# Lemming_SMD.net
KiCad netlist of a schematic drawn in EAGLE
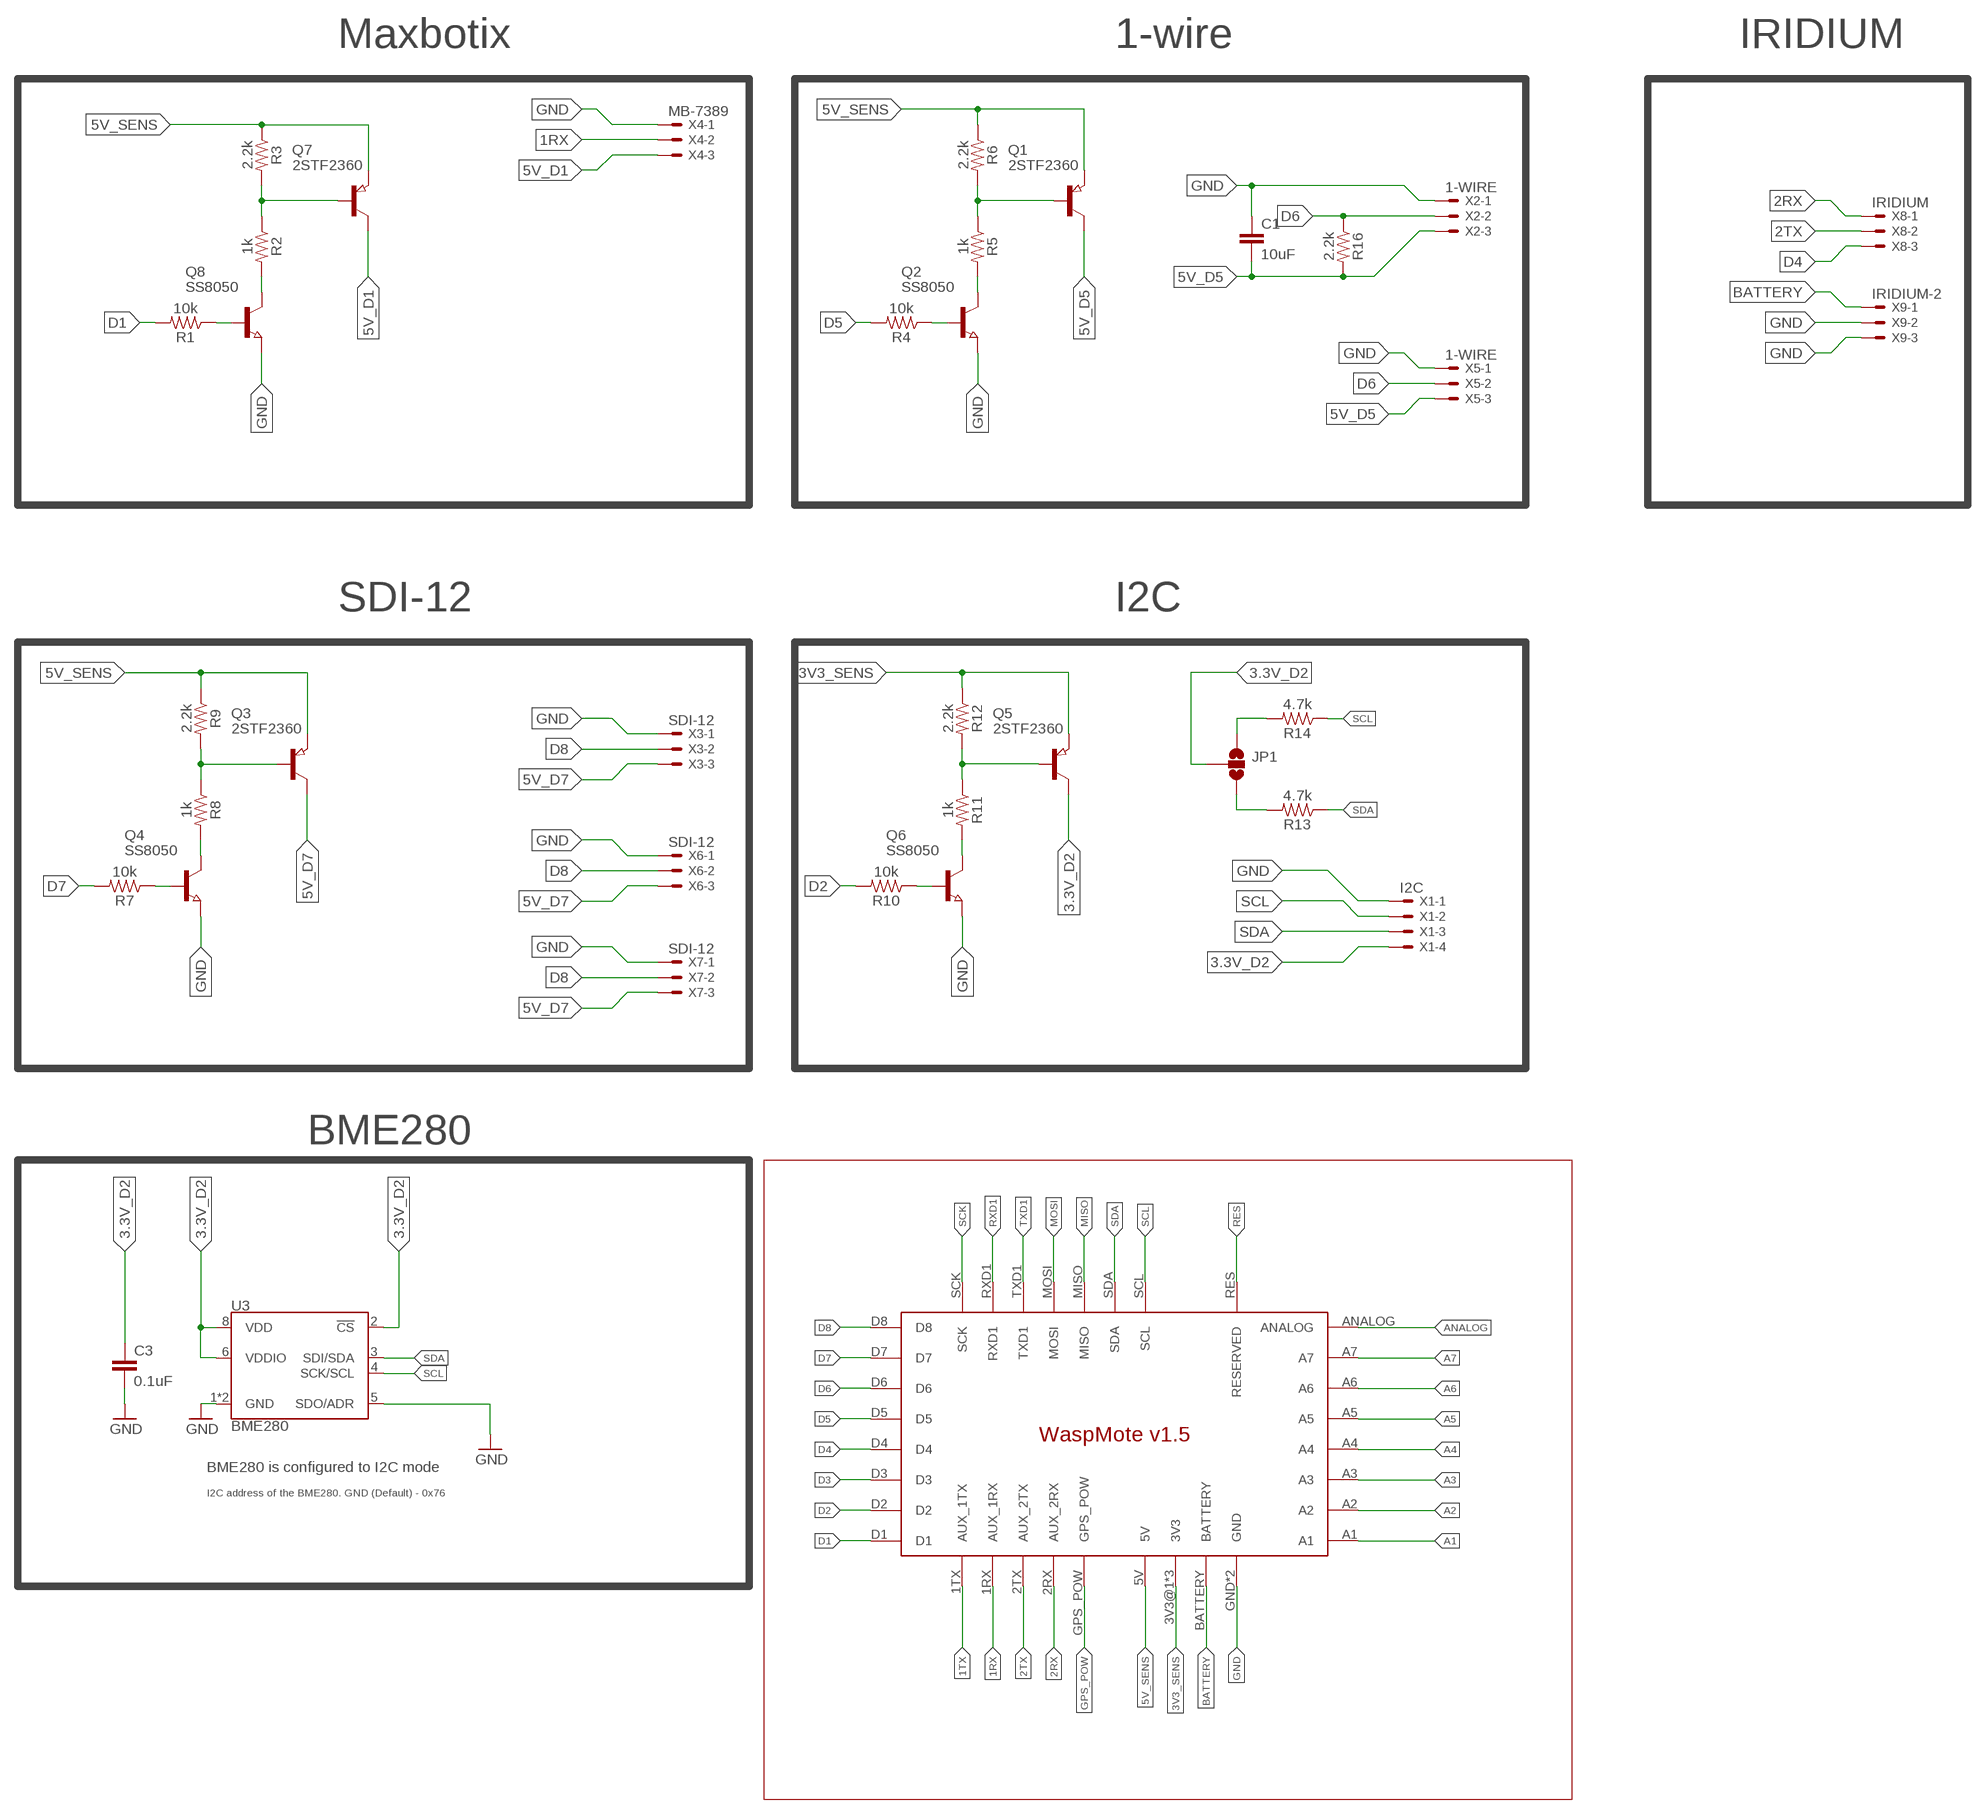
[diagram p0: schematic, sheet 1]

(export (version "E")
  (design (tool "Eeschema 10.0.6"))
  (components
    (comp (ref "C1")
      (value "10uF")
      (footprint "eagle-import:0603")
      (libsource (lib "eagle-import") (part "0.1UF-0603-25V-(+80/-20%)"))
    )
    (comp (ref "C3")
      (value "0.1uF")
      (footprint "eagle-import:0603")
      (libsource (lib "eagle-import") (part "0.1UF-0603-25V-(+80/-20%)"))
    )
    (comp (ref "JP1")
      (value "JUMPER-SMT_3_NO_SILK")
      (footprint "eagle-import:SMT-JUMPER_3_NO_SILK")
      (libsource (lib "eagle-import") (part "JUMPER-SMT_3_NO_SILK"))
    )
    (comp (ref "Q1")
      (value "2STF2360")
      (footprint "eagle-import:SOT89")
      (libsource (lib "eagle-import") (part "PNP-TRANSISTOR_SOT89"))
    )
    (comp (ref "Q2")
      (value "SS8050")
      (footprint "eagle-import:SOT23")
      (libsource (lib "eagle-import") (part "NPN-TRANSISTOR_SOT23"))
    )
    (comp (ref "Q3")
      (value "2STF2360")
      (footprint "eagle-import:SOT89")
      (libsource (lib "eagle-import") (part "PNP-TRANSISTOR_SOT89"))
    )
    (comp (ref "Q4")
      (value "SS8050")
      (footprint "eagle-import:SOT23")
      (libsource (lib "eagle-import") (part "NPN-TRANSISTOR_SOT23"))
    )
    (comp (ref "Q5")
      (value "2STF2360")
      (footprint "eagle-import:SOT89")
      (libsource (lib "eagle-import") (part "PNP-TRANSISTOR_SOT89"))
    )
    (comp (ref "Q6")
      (value "SS8050")
      (footprint "eagle-import:SOT23")
      (libsource (lib "eagle-import") (part "NPN-TRANSISTOR_SOT23"))
    )
    (comp (ref "Q7")
      (value "2STF2360")
      (footprint "eagle-import:SOT89")
      (libsource (lib "eagle-import") (part "PNP-TRANSISTOR_SOT89"))
    )
    (comp (ref "Q8")
      (value "SS8050")
      (footprint "eagle-import:SOT23")
      (libsource (lib "eagle-import") (part "NPN-TRANSISTOR_SOT23"))
    )
    (comp (ref "R1")
      (value "10k")
      (footprint "eagle-import:0603")
      (libsource (lib "eagle-import") (part "4.7KOHM-0603-1/10W-1%"))
    )
    (comp (ref "R2")
      (value "1k")
      (footprint "eagle-import:0603")
      (libsource (lib "eagle-import") (part "4.7KOHM-0603-1/10W-1%"))
    )
    (comp (ref "R3")
      (value "2.2k")
      (footprint "eagle-import:0603")
      (libsource (lib "eagle-import") (part "4.7KOHM-0603-1/10W-1%"))
    )
    (comp (ref "R4")
      (value "10k")
      (footprint "eagle-import:0603")
      (libsource (lib "eagle-import") (part "4.7KOHM-0603-1/10W-1%"))
    )
    (comp (ref "R5")
      (value "1k")
      (footprint "eagle-import:0603")
      (libsource (lib "eagle-import") (part "4.7KOHM-0603-1/10W-1%"))
    )
    (comp (ref "R6")
      (value "2.2k")
      (footprint "eagle-import:0603")
      (libsource (lib "eagle-import") (part "4.7KOHM-0603-1/10W-1%"))
    )
    (comp (ref "R7")
      (value "10k")
      (footprint "eagle-import:0603")
      (libsource (lib "eagle-import") (part "4.7KOHM-0603-1/10W-1%"))
    )
    (comp (ref "R8")
      (value "1k")
      (footprint "eagle-import:0603")
      (libsource (lib "eagle-import") (part "4.7KOHM-0603-1/10W-1%"))
    )
    (comp (ref "R9")
      (value "2.2k")
      (footprint "eagle-import:0603")
      (libsource (lib "eagle-import") (part "4.7KOHM-0603-1/10W-1%"))
    )
    (comp (ref "R10")
      (value "10k")
      (footprint "eagle-import:0603")
      (libsource (lib "eagle-import") (part "4.7KOHM-0603-1/10W-1%"))
    )
    (comp (ref "R11")
      (value "1k")
      (footprint "eagle-import:0603")
      (libsource (lib "eagle-import") (part "4.7KOHM-0603-1/10W-1%"))
    )
    (comp (ref "R12")
      (value "2.2k")
      (footprint "eagle-import:0603")
      (libsource (lib "eagle-import") (part "4.7KOHM-0603-1/10W-1%"))
    )
    (comp (ref "R13")
      (value "4.7k")
      (footprint "eagle-import:0603")
      (libsource (lib "eagle-import") (part "4.7KOHM-0603-1/10W-1%"))
    )
    (comp (ref "R14")
      (value "4.7k")
      (footprint "eagle-import:0603")
      (libsource (lib "eagle-import") (part "4.7KOHM-0603-1/10W-1%"))
    )
    (comp (ref "R16")
      (value "2.2k")
      (footprint "eagle-import:0603")
      (libsource (lib "eagle-import") (part "4.7KOHM-0603-1/10W-1%"))
    )
    (comp (ref "U$1")
      (value "WASPMOTE_V1.5")
      (footprint "eagle-import:WASPMOTE_V1.5")
      (libsource (lib "eagle-import") (part "WASPMOTE_V1.5"))
    )
    (comp (ref "U3")
      (value "BME280")
      (footprint "eagle-import:LGA-8-2.5X2.5")
      (libsource (lib "eagle-import") (part "BME280"))
    )
    (comp (ref "X1")
      (value "I2C")
      (footprint "eagle-import:22-23-2041")
      (fields (field (name "MF") "MOLEX") (field (name "MPN") "22-23-2041"))
      (libsource (lib "eagle-import") (part "22-23-2041"))
    )
    (comp (ref "X2")
      (value "1-WIRE")
      (footprint "eagle-import:22-23-2031")
      (fields (field (name "MF") "MOLEX") (field (name "MPN") "22-23-2031"))
      (libsource (lib "eagle-import") (part "22-23-2031"))
    )
    (comp (ref "X3")
      (value "SDI-12")
      (footprint "eagle-import:22-23-2031")
      (fields (field (name "MF") "MOLEX") (field (name "MPN") "22-23-2031"))
      (libsource (lib "eagle-import") (part "22-23-2031"))
    )
    (comp (ref "X4")
      (value "MB-7389")
      (footprint "eagle-import:22-23-2031")
      (fields (field (name "MF") "MOLEX") (field (name "MPN") "22-23-2031"))
      (libsource (lib "eagle-import") (part "22-23-2031"))
    )
    (comp (ref "X5")
      (value "1-WIRE")
      (footprint "eagle-import:22-23-2031")
      (fields (field (name "MF") "MOLEX") (field (name "MPN") "22-23-2031"))
      (libsource (lib "eagle-import") (part "22-23-2031"))
    )
    (comp (ref "X6")
      (value "SDI-12")
      (footprint "eagle-import:22-23-2031")
      (fields (field (name "MF") "MOLEX") (field (name "MPN") "22-23-2031"))
      (libsource (lib "eagle-import") (part "22-23-2031"))
    )
    (comp (ref "X7")
      (value "SDI-12")
      (footprint "eagle-import:22-23-2031")
      (fields (field (name "MF") "MOLEX") (field (name "MPN") "22-23-2031"))
      (libsource (lib "eagle-import") (part "22-23-2031"))
    )
    (comp (ref "X8")
      (value "IRIDIUM")
      (footprint "eagle-import:22-23-2031")
      (fields (field (name "MF") "MOLEX") (field (name "MPN") "22-23-2031"))
      (libsource (lib "eagle-import") (part "22-23-2031"))
    )
    (comp (ref "X9")
      (value "IRIDIUM-2")
      (footprint "eagle-import:22-23-2031")
      (fields (field (name "MF") "MOLEX") (field (name "MPN") "22-23-2031"))
      (libsource (lib "eagle-import") (part "22-23-2031"))
    )
  )
  (nets
    (net (code "1") (name "1RX") (class "Default")
      (node (ref "U$1") (pin "1RX") (pinfunction "AUX_1RX_1RX") (pintype "bidirectional"))
      (node (ref "X4") (pin "2") (pinfunction "S_2") (pintype "passive"))
    )
    (net (code "2") (name "1TX") (class "Default")
      (node (ref "U$1") (pin "1TX") (pinfunction "AUX_1TX_1TX") (pintype "bidirectional"))
    )
    (net (code "3") (name "2RX") (class "Default")
      (node (ref "U$1") (pin "2RX") (pinfunction "AUX_2RX_2RX") (pintype "bidirectional"))
      (node (ref "X8") (pin "1") (pinfunction "S_1") (pintype "passive"))
    )
    (net (code "4") (name "2TX") (class "Default")
      (node (ref "U$1") (pin "2TX") (pinfunction "AUX_2TX_2TX") (pintype "bidirectional"))
      (node (ref "X8") (pin "2") (pinfunction "S_2") (pintype "passive"))
    )
    (net (code "5") (name "3.3V_D2") (class "Default")
      (node (ref "C3") (pin "1") (pinfunction "1_1") (pintype "passive"))
      (node (ref "JP1") (pin "2") (pinfunction "2_2") (pintype "passive"))
      (node (ref "Q5") (pin "2") (pinfunction "C_2") (pintype "passive"))
      (node (ref "U3") (pin "2") (pinfunction "~{CS}_2") (pintype "bidirectional"))
      (node (ref "U3") (pin "6") (pinfunction "VDDIO_6") (pintype "bidirectional"))
      (node (ref "U3") (pin "8") (pinfunction "VDD_8") (pintype "bidirectional"))
      (node (ref "X1") (pin "4") (pinfunction "S_4") (pintype "passive"))
    )
    (net (code "6") (name "3V3_SENS") (class "Default")
      (node (ref "Q5") (pin "3") (pinfunction "E_3") (pintype "passive"))
      (node (ref "R12") (pin "1") (pinfunction "1_1") (pintype "passive"))
      (node (ref "U$1") (pin "3V3@1") (pinfunction "3V3_3V3@1") (pintype "bidirectional"))
      (node (ref "U$1") (pin "3V3@2") (pinfunction "3V3_3V3@2") (pintype "bidirectional"))
      (node (ref "U$1") (pin "3V3@3") (pinfunction "3V3_3V3@3") (pintype "bidirectional"))
    )
    (net (code "7") (name "5V_D1") (class "Default")
      (node (ref "Q7") (pin "2") (pinfunction "C_2") (pintype "passive"))
      (node (ref "X4") (pin "3") (pinfunction "S_3") (pintype "passive"))
    )
    (net (code "8") (name "5V_D5") (class "Default")
      (node (ref "C1") (pin "2") (pinfunction "2_2") (pintype "passive"))
      (node (ref "Q1") (pin "2") (pinfunction "C_2") (pintype "passive"))
      (node (ref "R16") (pin "2") (pinfunction "2_2") (pintype "passive"))
      (node (ref "X2") (pin "3") (pinfunction "S_3") (pintype "passive"))
      (node (ref "X5") (pin "3") (pinfunction "S_3") (pintype "passive"))
    )
    (net (code "9") (name "5V_D7") (class "Default")
      (node (ref "Q3") (pin "2") (pinfunction "C_2") (pintype "passive"))
      (node (ref "X3") (pin "3") (pinfunction "S_3") (pintype "passive"))
      (node (ref "X6") (pin "3") (pinfunction "S_3") (pintype "passive"))
      (node (ref "X7") (pin "3") (pinfunction "S_3") (pintype "passive"))
    )
    (net (code "10") (name "5V_SENS") (class "Default")
      (node (ref "Q1") (pin "3") (pinfunction "E_3") (pintype "passive"))
      (node (ref "Q3") (pin "3") (pinfunction "E_3") (pintype "passive"))
      (node (ref "Q7") (pin "3") (pinfunction "E_3") (pintype "passive"))
      (node (ref "R3") (pin "1") (pinfunction "1_1") (pintype "passive"))
      (node (ref "R6") (pin "1") (pinfunction "1_1") (pintype "passive"))
      (node (ref "R9") (pin "1") (pinfunction "1_1") (pintype "passive"))
      (node (ref "U$1") (pin "5V") (pinfunction "5V_5V") (pintype "bidirectional"))
    )
    (net (code "11") (name "A1") (class "Default")
      (node (ref "U$1") (pin "A1") (pinfunction "A1_A1") (pintype "bidirectional"))
    )
    (net (code "12") (name "A2") (class "Default")
      (node (ref "U$1") (pin "A2") (pinfunction "A2_A2") (pintype "bidirectional"))
    )
    (net (code "13") (name "A3") (class "Default")
      (node (ref "U$1") (pin "A3") (pinfunction "A3_A3") (pintype "bidirectional"))
    )
    (net (code "14") (name "A4") (class "Default")
      (node (ref "U$1") (pin "A4") (pinfunction "A4_A4") (pintype "bidirectional"))
    )
    (net (code "15") (name "A5") (class "Default")
      (node (ref "U$1") (pin "A5") (pinfunction "A5_A5") (pintype "bidirectional"))
    )
    (net (code "16") (name "A6") (class "Default")
      (node (ref "U$1") (pin "A6") (pinfunction "A6_A6") (pintype "bidirectional"))
    )
    (net (code "17") (name "A7") (class "Default")
      (node (ref "U$1") (pin "A7") (pinfunction "A7_A7") (pintype "bidirectional"))
    )
    (net (code "18") (name "ANALOG") (class "Default")
      (node (ref "U$1") (pin "ANALOG") (pinfunction "ANALOG_ANALOG") (pintype "bidirectional"))
    )
    (net (code "19") (name "BATTERY") (class "Default")
      (node (ref "U$1") (pin "BATTERY") (pinfunction "BATTERY_BATTERY") (pintype "bidirectional"))
      (node (ref "X9") (pin "1") (pinfunction "S_1") (pintype "passive"))
    )
    (net (code "20") (name "D1") (class "Default")
      (node (ref "R1") (pin "2") (pinfunction "2_2") (pintype "passive"))
      (node (ref "U$1") (pin "D1") (pinfunction "D1_D1") (pintype "bidirectional"))
    )
    (net (code "21") (name "D2") (class "Default")
      (node (ref "R10") (pin "2") (pinfunction "2_2") (pintype "passive"))
      (node (ref "U$1") (pin "D2") (pinfunction "D2_D2") (pintype "bidirectional"))
    )
    (net (code "22") (name "D3") (class "Default")
      (node (ref "U$1") (pin "D3") (pinfunction "D3_D3") (pintype "bidirectional"))
    )
    (net (code "23") (name "D4") (class "Default")
      (node (ref "U$1") (pin "D4") (pinfunction "D4_D4") (pintype "bidirectional"))
      (node (ref "X8") (pin "3") (pinfunction "S_3") (pintype "passive"))
    )
    (net (code "24") (name "D5") (class "Default")
      (node (ref "R4") (pin "2") (pinfunction "2_2") (pintype "passive"))
      (node (ref "U$1") (pin "D5") (pinfunction "D5_D5") (pintype "bidirectional"))
    )
    (net (code "25") (name "D6") (class "Default")
      (node (ref "R16") (pin "1") (pinfunction "1_1") (pintype "passive"))
      (node (ref "U$1") (pin "D6") (pinfunction "D6_D6") (pintype "bidirectional"))
      (node (ref "X2") (pin "2") (pinfunction "S_2") (pintype "passive"))
      (node (ref "X5") (pin "2") (pinfunction "S_2") (pintype "passive"))
    )
    (net (code "26") (name "D7") (class "Default")
      (node (ref "R7") (pin "2") (pinfunction "2_2") (pintype "passive"))
      (node (ref "U$1") (pin "D7") (pinfunction "D7_D7") (pintype "bidirectional"))
    )
    (net (code "27") (name "D8") (class "Default")
      (node (ref "U$1") (pin "D8") (pinfunction "D8_D8") (pintype "bidirectional"))
      (node (ref "X3") (pin "2") (pinfunction "S_2") (pintype "passive"))
      (node (ref "X6") (pin "2") (pinfunction "S_2") (pintype "passive"))
      (node (ref "X7") (pin "2") (pinfunction "S_2") (pintype "passive"))
    )
    (net (code "28") (name "GND") (class "Default")
      (node (ref "C1") (pin "1") (pinfunction "1_1") (pintype "passive"))
      (node (ref "C3") (pin "2") (pinfunction "2_2") (pintype "passive"))
      (node (ref "Q2") (pin "2") (pinfunction "E_2") (pintype "passive"))
      (node (ref "Q4") (pin "2") (pinfunction "E_2") (pintype "passive"))
      (node (ref "Q6") (pin "2") (pinfunction "E_2") (pintype "passive"))
      (node (ref "Q8") (pin "2") (pinfunction "E_2") (pintype "passive"))
      (node (ref "U$1") (pin "GND") (pinfunction "GND_GND") (pintype "bidirectional"))
      (node (ref "U$1") (pin "GND_2") (pinfunction "GND_GND_2") (pintype "bidirectional"))
      (node (ref "U3") (pin "1") (pinfunction "GND_1") (pintype "bidirectional"))
      (node (ref "U3") (pin "5") (pinfunction "SDO/ADR_5") (pintype "bidirectional"))
      (node (ref "U3") (pin "7") (pinfunction "GND_7") (pintype "bidirectional"))
      (node (ref "X1") (pin "1") (pinfunction "S_1") (pintype "passive"))
      (node (ref "X2") (pin "1") (pinfunction "S_1") (pintype "passive"))
      (node (ref "X3") (pin "1") (pinfunction "S_1") (pintype "passive"))
      (node (ref "X4") (pin "1") (pinfunction "S_1") (pintype "passive"))
      (node (ref "X5") (pin "1") (pinfunction "S_1") (pintype "passive"))
      (node (ref "X6") (pin "1") (pinfunction "S_1") (pintype "passive"))
      (node (ref "X7") (pin "1") (pinfunction "S_1") (pintype "passive"))
      (node (ref "X9") (pin "2") (pinfunction "S_2") (pintype "passive"))
      (node (ref "X9") (pin "3") (pinfunction "S_3") (pintype "passive"))
    )
    (net (code "29") (name "GPS_POW") (class "Default")
      (node (ref "U$1") (pin "GPS_POW") (pinfunction "GPS_POW_GPS_POW") (pintype "bidirectional"))
    )
    (net (code "30") (name "MISO") (class "Default")
      (node (ref "U$1") (pin "MISO") (pinfunction "MISO_MISO") (pintype "bidirectional"))
    )
    (net (code "31") (name "MOSI") (class "Default")
      (node (ref "U$1") (pin "MOSI") (pinfunction "MOSI_MOSI") (pintype "bidirectional"))
    )
    (net (code "32") (name "Net-(JP1-Pad1)") (class "Default")
      (node (ref "JP1") (pin "1") (pinfunction "1_1") (pintype "passive"))
      (node (ref "R14") (pin "2") (pinfunction "2_2") (pintype "passive"))
    )
    (net (code "33") (name "Net-(JP1-Pad3)") (class "Default")
      (node (ref "JP1") (pin "3") (pinfunction "3_3") (pintype "passive"))
      (node (ref "R13") (pin "2") (pinfunction "2_2") (pintype "passive"))
    )
    (net (code "34") (name "Net-(Q1-B)") (class "Default")
      (node (ref "Q1") (pin "1") (pinfunction "B_1") (pintype "passive"))
      (node (ref "R5") (pin "1") (pinfunction "1_1") (pintype "passive"))
      (node (ref "R6") (pin "2") (pinfunction "2_2") (pintype "passive"))
    )
    (net (code "35") (name "Net-(Q2-B)") (class "Default")
      (node (ref "Q2") (pin "1") (pinfunction "B_1") (pintype "passive"))
      (node (ref "R4") (pin "1") (pinfunction "1_1") (pintype "passive"))
    )
    (net (code "36") (name "Net-(Q2-C)") (class "Default")
      (node (ref "Q2") (pin "3") (pinfunction "C_3") (pintype "passive"))
      (node (ref "R5") (pin "2") (pinfunction "2_2") (pintype "passive"))
    )
    (net (code "37") (name "Net-(Q3-B)") (class "Default")
      (node (ref "Q3") (pin "1") (pinfunction "B_1") (pintype "passive"))
      (node (ref "R8") (pin "1") (pinfunction "1_1") (pintype "passive"))
      (node (ref "R9") (pin "2") (pinfunction "2_2") (pintype "passive"))
    )
    (net (code "38") (name "Net-(Q4-B)") (class "Default")
      (node (ref "Q4") (pin "1") (pinfunction "B_1") (pintype "passive"))
      (node (ref "R7") (pin "1") (pinfunction "1_1") (pintype "passive"))
    )
    (net (code "39") (name "Net-(Q4-C)") (class "Default")
      (node (ref "Q4") (pin "3") (pinfunction "C_3") (pintype "passive"))
      (node (ref "R8") (pin "2") (pinfunction "2_2") (pintype "passive"))
    )
    (net (code "40") (name "Net-(Q5-B)") (class "Default")
      (node (ref "Q5") (pin "1") (pinfunction "B_1") (pintype "passive"))
      (node (ref "R11") (pin "1") (pinfunction "1_1") (pintype "passive"))
      (node (ref "R12") (pin "2") (pinfunction "2_2") (pintype "passive"))
    )
    (net (code "41") (name "Net-(Q6-B)") (class "Default")
      (node (ref "Q6") (pin "1") (pinfunction "B_1") (pintype "passive"))
      (node (ref "R10") (pin "1") (pinfunction "1_1") (pintype "passive"))
    )
    (net (code "42") (name "Net-(Q6-C)") (class "Default")
      (node (ref "Q6") (pin "3") (pinfunction "C_3") (pintype "passive"))
      (node (ref "R11") (pin "2") (pinfunction "2_2") (pintype "passive"))
    )
    (net (code "43") (name "Net-(Q7-B)") (class "Default")
      (node (ref "Q7") (pin "1") (pinfunction "B_1") (pintype "passive"))
      (node (ref "R2") (pin "1") (pinfunction "1_1") (pintype "passive"))
      (node (ref "R3") (pin "2") (pinfunction "2_2") (pintype "passive"))
    )
    (net (code "44") (name "Net-(Q8-B)") (class "Default")
      (node (ref "Q8") (pin "1") (pinfunction "B_1") (pintype "passive"))
      (node (ref "R1") (pin "1") (pinfunction "1_1") (pintype "passive"))
    )
    (net (code "45") (name "Net-(Q8-C)") (class "Default")
      (node (ref "Q8") (pin "3") (pinfunction "C_3") (pintype "passive"))
      (node (ref "R2") (pin "2") (pinfunction "2_2") (pintype "passive"))
    )
    (net (code "46") (name "RES") (class "Default")
      (node (ref "U$1") (pin "RES") (pinfunction "RESERVED_RES") (pintype "bidirectional"))
    )
    (net (code "47") (name "RXD1") (class "Default")
      (node (ref "U$1") (pin "RXD1") (pinfunction "RXD1_RXD1") (pintype "bidirectional"))
    )
    (net (code "48") (name "SCK") (class "Default")
      (node (ref "U$1") (pin "SCK") (pinfunction "SCK_SCK") (pintype "bidirectional"))
    )
    (net (code "49") (name "SCL") (class "Default")
      (node (ref "R14") (pin "1") (pinfunction "1_1") (pintype "passive"))
      (node (ref "U$1") (pin "SCL") (pinfunction "SCL_SCL") (pintype "bidirectional"))
      (node (ref "U3") (pin "4") (pinfunction "SCK/SCL_4") (pintype "bidirectional"))
      (node (ref "X1") (pin "2") (pinfunction "S_2") (pintype "passive"))
    )
    (net (code "50") (name "SDA") (class "Default")
      (node (ref "R13") (pin "1") (pinfunction "1_1") (pintype "passive"))
      (node (ref "U$1") (pin "SDA") (pinfunction "SDA_SDA") (pintype "bidirectional"))
      (node (ref "U3") (pin "3") (pinfunction "SDI/SDA_3") (pintype "bidirectional"))
      (node (ref "X1") (pin "3") (pinfunction "S_3") (pintype "passive"))
    )
    (net (code "51") (name "TXD1") (class "Default")
      (node (ref "U$1") (pin "TXD1") (pinfunction "TXD1_TXD1") (pintype "bidirectional"))
    )
  )
)
